# Sheet_1_2024-04-09.net
KiCad netlist of a schematic drawn in EasyEDA Pro
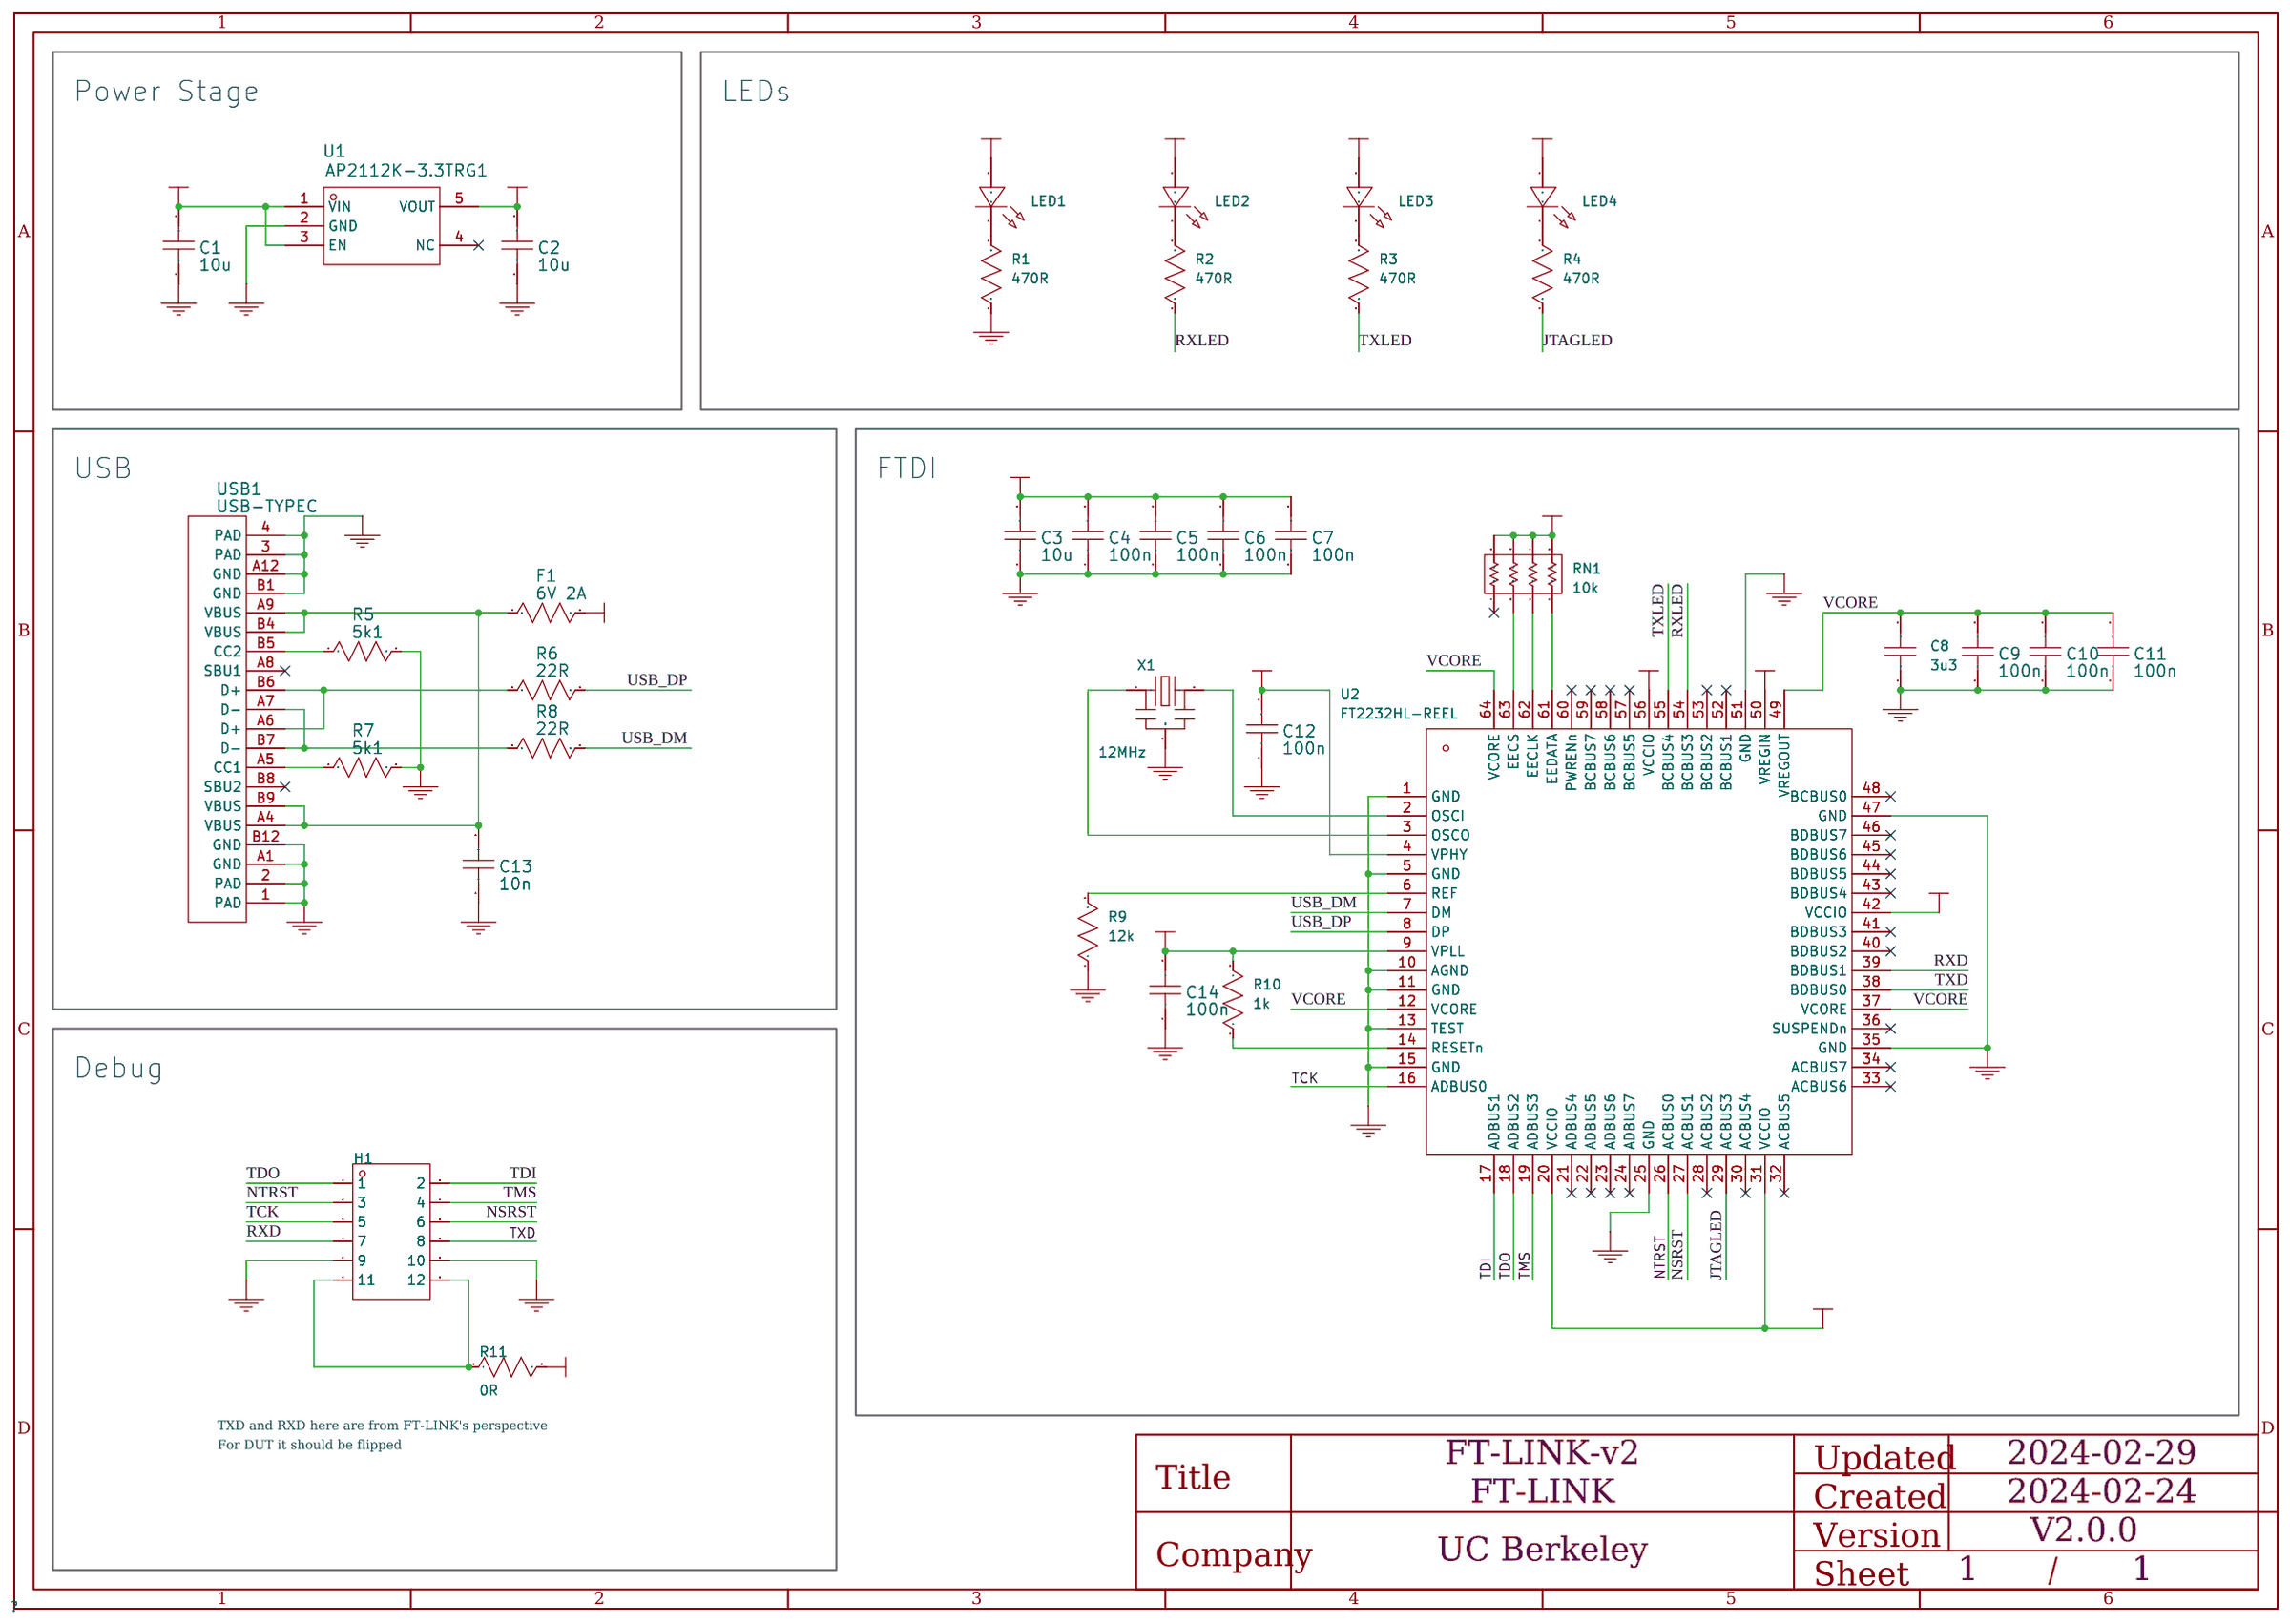
[diagram p0: schematic sheet]

(export (version "E")
  (design (tool "Eeschema 10.0.6"))
  (components
    (comp (ref "C1")
      (value "10u")
      (footprint "easyedapro:CAPA-0603")
      (fields (field (name "Manufacturer Part") "CL10A106KP8NNNC") (field (name "Manufacturer") "SAMSUNG"))
      (libsource (lib "easyedapro") (part "10u"))
    )
    (comp (ref "C2")
      (value "10u")
      (footprint "easyedapro:CAPA-0603")
      (fields (field (name "Manufacturer Part") "CL10A106KP8NNNC") (field (name "Manufacturer") "SAMSUNG"))
      (libsource (lib "easyedapro") (part "10u"))
    )
    (comp (ref "C3")
      (value "10u")
      (footprint "easyedapro:CAPA-0603")
      (fields (field (name "Manufacturer Part") "CL10A106KP8NNNC") (field (name "Manufacturer") "SAMSUNG"))
      (libsource (lib "easyedapro") (part "10u"))
    )
    (comp (ref "C4")
      (value "100n")
      (footprint "easyedapro:CAPA-0402")
      (fields (field (name "Manufacturer Part") "CL05B104KB54PNC") (field (name "Manufacturer") "SAMSUNG"))
      (libsource (lib "easyedapro") (part "100n"))
    )
    (comp (ref "C5")
      (value "100n")
      (footprint "easyedapro:CAPA-0402")
      (fields (field (name "Manufacturer Part") "CL05B104KB54PNC") (field (name "Manufacturer") "SAMSUNG"))
      (libsource (lib "easyedapro") (part "100n"))
    )
    (comp (ref "C6")
      (value "100n")
      (footprint "easyedapro:CAPA-0402")
      (fields (field (name "Manufacturer Part") "CL05B104KB54PNC") (field (name "Manufacturer") "SAMSUNG"))
      (libsource (lib "easyedapro") (part "100n"))
    )
    (comp (ref "C7")
      (value "100n")
      (footprint "easyedapro:CAPA-0402")
      (fields (field (name "Manufacturer Part") "CL05B104KB54PNC") (field (name "Manufacturer") "SAMSUNG"))
      (libsource (lib "easyedapro") (part "100n"))
    )
    (comp (ref "C8")
      (value "3u3")
      (footprint "easyedapro:CAPA-0603")
      (description "3.3uF ±10% 25V X5R")
      (fields (field (name "Manufacturer Part") "C1608X5R1E335KT000E") (field (name "Manufacturer") "TDK"))
      (libsource (lib "easyedapro") (part "CAPA-0603_3u3_25V"))
    )
    (comp (ref "C9")
      (value "100n")
      (footprint "easyedapro:CAPA-0402")
      (fields (field (name "Manufacturer Part") "CL05B104KB54PNC") (field (name "Manufacturer") "SAMSUNG"))
      (libsource (lib "easyedapro") (part "100n"))
    )
    (comp (ref "C10")
      (value "100n")
      (footprint "easyedapro:CAPA-0402")
      (fields (field (name "Manufacturer Part") "CL05B104KB54PNC") (field (name "Manufacturer") "SAMSUNG"))
      (libsource (lib "easyedapro") (part "100n"))
    )
    (comp (ref "C11")
      (value "100n")
      (footprint "easyedapro:CAPA-0402")
      (fields (field (name "Manufacturer Part") "CL05B104KB54PNC") (field (name "Manufacturer") "SAMSUNG"))
      (libsource (lib "easyedapro") (part "100n"))
    )
    (comp (ref "C12")
      (value "100n")
      (footprint "easyedapro:CAPA-0402")
      (fields (field (name "Manufacturer Part") "CL05B104KB54PNC") (field (name "Manufacturer") "SAMSUNG"))
      (libsource (lib "easyedapro") (part "100n"))
    )
    (comp (ref "C13")
      (value "10n")
      (footprint "easyedapro:CAPA-0402")
      (fields (field (name "Manufacturer Part") "CL05B103KB5NNNC") (field (name "Manufacturer") "SAMSUNG"))
      (libsource (lib "easyedapro") (part "10n"))
    )
    (comp (ref "C14")
      (value "100n")
      (footprint "easyedapro:CAPA-0402")
      (fields (field (name "Manufacturer Part") "CL05B104KB54PNC") (field (name "Manufacturer") "SAMSUNG"))
      (libsource (lib "easyedapro") (part "100n"))
    )
    (comp (ref "F1")
      (value "6V 2A")
      (footprint "easyedapro:R0805")
      (fields (field (name "Manufacturer Part") "SL0805200") (field (name "Manufacturer") "TECHFUSE"))
      (libsource (lib "easyedapro") (part "6V 2A"))
    )
    (comp (ref "H1")
      (value "~")
      (footprint "easyedapro:CONN-TH_A2541WR-2X6P")
      (fields (field (name "Manufacturer Part") "A2541WR-2x6P") (field (name "Manufacturer") "CJT 长江连接器"))
      (libsource (lib "easyedapro") (part "A2541WR-2X6P"))
    )
    (comp (ref "LED1")
      (value "~")
      (footprint "easyedapro:LED-0603")
      (description "红灯 632nm")
      (fields
        (field (name "Manufacturer Part") "19-217/R6C-AL1M2VY/3T")
        (field (name "Manufacturer") "EVERLIGHT 台湾亿光")
      )
      (libsource (lib "easyedapro") (part "LED-0603_R"))
    )
    (comp (ref "LED2")
      (value "~")
      (footprint "easyedapro:LED-0603")
      (description "白灯 高亮")
      (fields (field (name "Manufacturer Part") "LED White") (field (name "Manufacturer") "KENTO"))
      (libsource (lib "easyedapro") (part "LED-0603_W"))
    )
    (comp (ref "LED3")
      (value "~")
      (footprint "easyedapro:LED-0603")
      (description "白灯 高亮")
      (fields (field (name "Manufacturer Part") "LED White") (field (name "Manufacturer") "KENTO"))
      (libsource (lib "easyedapro") (part "LED-0603_W"))
    )
    (comp (ref "LED4")
      (value "~")
      (footprint "easyedapro:LED-0603")
      (description "蓝灯 高亮")
      (fields (field (name "Manufacturer Part") "XL-0603QBC") (field (name "Manufacturer") "KENTO"))
      (libsource (lib "easyedapro") (part "LED-0603_B"))
    )
    (comp (ref "R1")
      (value "470R")
      (footprint "easyedapro:RES-0402")
      (description "厚膜电阻 470Ω ±1% 62.5mW")
      (fields (field (name "Manufacturer Part") "0402WGF4700TCE") (field (name "Manufacturer") "UniOhm 台湾厚声"))
      (libsource (lib "easyedapro") (part "RES-0402_470R"))
    )
    (comp (ref "R2")
      (value "470R")
      (footprint "easyedapro:RES-0402")
      (description "厚膜电阻 470Ω ±1% 62.5mW")
      (fields (field (name "Manufacturer Part") "0402WGF4700TCE") (field (name "Manufacturer") "UniOhm 台湾厚声"))
      (libsource (lib "easyedapro") (part "RES-0402_470R"))
    )
    (comp (ref "R3")
      (value "470R")
      (footprint "easyedapro:RES-0402")
      (description "厚膜电阻 470Ω ±1% 62.5mW")
      (fields (field (name "Manufacturer Part") "0402WGF4700TCE") (field (name "Manufacturer") "UniOhm 台湾厚声"))
      (libsource (lib "easyedapro") (part "RES-0402_470R"))
    )
    (comp (ref "R4")
      (value "470R")
      (footprint "easyedapro:RES-0402")
      (description "厚膜电阻 470Ω ±1% 62.5mW")
      (fields (field (name "Manufacturer Part") "0402WGF4700TCE") (field (name "Manufacturer") "UniOhm 台湾厚声"))
      (libsource (lib "easyedapro") (part "RES-0402_470R"))
    )
    (comp (ref "R5")
      (value "5k1")
      (footprint "easyedapro:RES-0402")
      (fields (field (name "Manufacturer Part") "0402WGF5101TCE") (field (name "Manufacturer") "UniOhm 台湾厚声"))
      (libsource (lib "easyedapro") (part "5k1"))
    )
    (comp (ref "R6")
      (value "22R")
      (footprint "easyedapro:RES-0402")
      (fields (field (name "Manufacturer Part") "0402WGF220JTCE") (field (name "Manufacturer") "UniOhm 台湾厚声"))
      (libsource (lib "easyedapro") (part "22R"))
    )
    (comp (ref "R7")
      (value "5k1")
      (footprint "easyedapro:RES-0402")
      (fields (field (name "Manufacturer Part") "0402WGF5101TCE") (field (name "Manufacturer") "UniOhm 台湾厚声"))
      (libsource (lib "easyedapro") (part "5k1"))
    )
    (comp (ref "R8")
      (value "22R")
      (footprint "easyedapro:RES-0402")
      (fields (field (name "Manufacturer Part") "0402WGF220JTCE") (field (name "Manufacturer") "UniOhm 台湾厚声"))
      (libsource (lib "easyedapro") (part "22R"))
    )
    (comp (ref "R9")
      (value "12k")
      (footprint "easyedapro:RES-0402")
      (description "厚膜电阻 12kΩ ±1% 62.5mW")
      (fields (field (name "Manufacturer Part") "0402WGF1202TCE") (field (name "Manufacturer") "UniOhm 台湾厚声"))
      (libsource (lib "easyedapro") (part "RES-0402_12k"))
    )
    (comp (ref "R10")
      (value "1k")
      (footprint "easyedapro:RES-0402")
      (description "厚膜电阻 1kΩ ±1% 62.5mW")
      (fields (field (name "Manufacturer Part") "0402WGF1001TCE") (field (name "Manufacturer") "UniOhm 台湾厚声"))
      (libsource (lib "easyedapro") (part "RES-0402_1k"))
    )
    (comp (ref "R11")
      (value "0R")
      (footprint "easyedapro:RES-0402-TIE")
      (libsource (lib "easyedapro") (part "RES-0402_TIE"))
    )
    (comp (ref "RN1")
      (value "10k")
      (footprint "easyedapro:RES-ARRAY-SMD_0402-8P-L2.0-W1.0-BL")
      (description "10kΩ ±1% 0402x4")
      (fields (field (name "Manufacturer Part") "YC124-FR-0710KL") (field (name "Manufacturer") "YAGEO 国巨"))
      (libsource (lib "easyedapro") (part "RES-0402x4_10k"))
    )
    (comp (ref "U1")
      (value "AP2112K-3.3TRG1")
      (footprint "easyedapro:SOT-25-5_L3.0-W1.8-P0.95-LS3.0-BR")
      (fields (field (name "Manufacturer") "DIODES"))
      (libsource (lib "easyedapro") (part "AP2112K-3.3TRG1"))
    )
    (comp (ref "U2")
      (value "FT2232HL-REEL")
      (footprint "easyedapro:LQFP-64_L10.0-W10.0-P0.50-LS12.0-TL")
      (description "应用功能:USB转UART；USB转FIFO;接口协议:UART;")
      (fields (field (name "Manufacturer") "FTDI"))
      (libsource (lib "easyedapro") (part "FT2232HL"))
    )
    (comp (ref "USB1")
      (value "USB-TYPEC")
      (footprint "easyedapro:USB-C-SMD_KH-TYPE-C-16P")
      (fields
        (field (name "Manufacturer Part") "KH-TYPE-C-16P")
        (field (name "Manufacturer") "Shenzhen Kinghelm Elec")
      )
      (libsource (lib "easyedapro") (part "USB-TYPEC"))
    )
    (comp (ref "X1")
      (value "12MHz")
      (footprint "easyedapro:OSC-SMD_3P-L3.2-W1.3-P1.2-L")
      (description "频率:12MHz;内置负载电容:33pF;谐振阻抗:30Ω;")
      (fields
        (field (name "Manufacturer Part") "CSTNE12M0GH5C000R0")
        (field (name "Manufacturer") "muRata 村田")
      )
      (libsource (lib "easyedapro") (part "CSTNE12M0GH5C000R0"))
    )
  )
  (nets
    (net (code "1") (name "/JTAGLED") (class "Default")
      (node (ref "R4") (pin "1") (pinfunction "1_1") (pintype "input"))
      (node (ref "U2") (pin "29") (pinfunction "ACBUS3_29") (pintype "input"))
    )
    (net (code "2") (name "/NSRST") (class "Default")
      (node (ref "H1") (pin "6") (pinfunction "6_6") (pintype "input"))
      (node (ref "U2") (pin "27") (pinfunction "ACBUS1_27") (pintype "input"))
    )
    (net (code "3") (name "/NTRST") (class "Default")
      (node (ref "H1") (pin "3") (pinfunction "3_3") (pintype "input"))
      (node (ref "U2") (pin "26") (pinfunction "ACBUS0_26") (pintype "input"))
    )
    (net (code "4") (name "/RXD") (class "Default")
      (node (ref "H1") (pin "7") (pinfunction "7_7") (pintype "input"))
      (node (ref "U2") (pin "39") (pinfunction "BDBUS1_39") (pintype "input"))
    )
    (net (code "5") (name "/RXLED") (class "Default")
      (node (ref "R2") (pin "1") (pinfunction "1_1") (pintype "input"))
      (node (ref "U2") (pin "54") (pinfunction "BCBUS3_54") (pintype "input"))
    )
    (net (code "6") (name "/TCK") (class "Default")
      (node (ref "H1") (pin "5") (pinfunction "5_5") (pintype "input"))
      (node (ref "U2") (pin "16") (pinfunction "ADBUS0_16") (pintype "input"))
    )
    (net (code "7") (name "/TDI") (class "Default")
      (node (ref "H1") (pin "2") (pinfunction "2_2") (pintype "input"))
      (node (ref "U2") (pin "17") (pinfunction "ADBUS1_17") (pintype "input"))
    )
    (net (code "8") (name "/TDO") (class "Default")
      (node (ref "H1") (pin "1") (pinfunction "1_1") (pintype "input"))
      (node (ref "U2") (pin "18") (pinfunction "ADBUS2_18") (pintype "input"))
    )
    (net (code "9") (name "/TMS") (class "Default")
      (node (ref "H1") (pin "4") (pinfunction "4_4") (pintype "input"))
      (node (ref "U2") (pin "19") (pinfunction "ADBUS3_19") (pintype "input"))
    )
    (net (code "10") (name "/TXD") (class "Default")
      (node (ref "H1") (pin "8") (pinfunction "8_8") (pintype "input"))
      (node (ref "U2") (pin "38") (pinfunction "BDBUS0_38") (pintype "input"))
    )
    (net (code "11") (name "/TXLED") (class "Default")
      (node (ref "R3") (pin "1") (pinfunction "1_1") (pintype "input"))
      (node (ref "U2") (pin "55") (pinfunction "BCBUS4_55") (pintype "input"))
    )
    (net (code "12") (name "/USB_DM") (class "Default")
      (node (ref "R8") (pin "2") (pinfunction "2_2") (pintype "input"))
      (node (ref "U2") (pin "7") (pinfunction "DM_7") (pintype "input"))
    )
    (net (code "13") (name "/USB_DP") (class "Default")
      (node (ref "R6") (pin "2") (pinfunction "2_2") (pintype "input"))
      (node (ref "U2") (pin "8") (pinfunction "DP_8") (pintype "input"))
    )
    (net (code "14") (name "/VCORE") (class "Default")
      (node (ref "C10") (pin "2") (pinfunction "2_2") (pintype "input"))
      (node (ref "C11") (pin "2") (pinfunction "2_2") (pintype "input"))
      (node (ref "C8") (pin "1") (pinfunction "1_1") (pintype "input"))
      (node (ref "C9") (pin "2") (pinfunction "2_2") (pintype "input"))
      (node (ref "U2") (pin "12") (pinfunction "VCORE_12") (pintype "input"))
      (node (ref "U2") (pin "37") (pinfunction "VCORE_37") (pintype "input"))
      (node (ref "U2") (pin "49") (pinfunction "VREGOUT_49") (pintype "input"))
      (node (ref "U2") (pin "64") (pinfunction "VCORE_64") (pintype "input"))
    )
    (net (code "15") (name "3V3") (class "Default")
      (node (ref "C12") (pin "2") (pinfunction "2_2") (pintype "input"))
      (node (ref "C14") (pin "2") (pinfunction "2_2") (pintype "input"))
      (node (ref "C2") (pin "2") (pinfunction "2_2") (pintype "input"))
      (node (ref "C3") (pin "2") (pinfunction "2_2") (pintype "input"))
      (node (ref "C4") (pin "2") (pinfunction "2_2") (pintype "input"))
      (node (ref "C5") (pin "2") (pinfunction "2_2") (pintype "input"))
      (node (ref "C6") (pin "2") (pinfunction "2_2") (pintype "input"))
      (node (ref "C7") (pin "2") (pinfunction "2_2") (pintype "input"))
      (node (ref "LED1") (pin "2") (pinfunction "2_2") (pintype "input"))
      (node (ref "LED2") (pin "2") (pinfunction "2_2") (pintype "input"))
      (node (ref "LED3") (pin "2") (pinfunction "2_2") (pintype "input"))
      (node (ref "LED4") (pin "2") (pinfunction "2_2") (pintype "input"))
      (node (ref "R10") (pin "2") (pinfunction "2_2") (pintype "input"))
      (node (ref "R11") (pin "2") (pinfunction "2_2") (pintype "input"))
      (node (ref "RN1") (pin "5") (pinfunction "5_5") (pintype "input"))
      (node (ref "RN1") (pin "6") (pinfunction "6_6") (pintype "input"))
      (node (ref "RN1") (pin "7") (pinfunction "7_7") (pintype "input"))
      (node (ref "RN1") (pin "8") (pinfunction "8_8") (pintype "input"))
      (node (ref "U1") (pin "5") (pinfunction "VOUT_5") (pintype "input"))
      (node (ref "U2") (pin "20") (pinfunction "VCCIO_20") (pintype "input"))
      (node (ref "U2") (pin "31") (pinfunction "VCCIO_31") (pintype "input"))
      (node (ref "U2") (pin "4") (pinfunction "VPHY_4") (pintype "input"))
      (node (ref "U2") (pin "42") (pinfunction "VCCIO_42") (pintype "input"))
      (node (ref "U2") (pin "50") (pinfunction "VREGIN_50") (pintype "input"))
      (node (ref "U2") (pin "56") (pinfunction "VCCIO_56") (pintype "input"))
      (node (ref "U2") (pin "9") (pinfunction "VPLL_9") (pintype "input"))
    )
    (net (code "16") (name "5V") (class "Default")
      (node (ref "C1") (pin "2") (pinfunction "2_2") (pintype "input"))
      (node (ref "F1") (pin "2") (pinfunction "2_2") (pintype "input"))
      (node (ref "U1") (pin "1") (pinfunction "VIN_1") (pintype "input"))
      (node (ref "U1") (pin "3") (pinfunction "EN_3") (pintype "input"))
    )
    (net (code "17") (name "GND") (class "Default")
      (node (ref "C1") (pin "1") (pinfunction "1_1") (pintype "input"))
      (node (ref "C10") (pin "1") (pinfunction "1_1") (pintype "input"))
      (node (ref "C11") (pin "1") (pinfunction "1_1") (pintype "input"))
      (node (ref "C12") (pin "1") (pinfunction "1_1") (pintype "input"))
      (node (ref "C13") (pin "1") (pinfunction "1_1") (pintype "input"))
      (node (ref "C14") (pin "1") (pinfunction "1_1") (pintype "input"))
      (node (ref "C2") (pin "1") (pinfunction "1_1") (pintype "input"))
      (node (ref "C3") (pin "1") (pinfunction "1_1") (pintype "input"))
      (node (ref "C4") (pin "1") (pinfunction "1_1") (pintype "input"))
      (node (ref "C5") (pin "1") (pinfunction "1_1") (pintype "input"))
      (node (ref "C6") (pin "1") (pinfunction "1_1") (pintype "input"))
      (node (ref "C7") (pin "1") (pinfunction "1_1") (pintype "input"))
      (node (ref "C8") (pin "2") (pinfunction "2_2") (pintype "input"))
      (node (ref "C9") (pin "1") (pinfunction "1_1") (pintype "input"))
      (node (ref "H1") (pin "10") (pinfunction "10_10") (pintype "input"))
      (node (ref "H1") (pin "9") (pinfunction "9_9") (pintype "input"))
      (node (ref "R1") (pin "1") (pinfunction "1_1") (pintype "input"))
      (node (ref "R5") (pin "2") (pinfunction "2_2") (pintype "input"))
      (node (ref "R7") (pin "2") (pinfunction "2_2") (pintype "input"))
      (node (ref "R9") (pin "1") (pinfunction "1_1") (pintype "input"))
      (node (ref "U1") (pin "2") (pinfunction "GND_2") (pintype "input"))
      (node (ref "U2") (pin "1") (pinfunction "GND_1") (pintype "input"))
      (node (ref "U2") (pin "10") (pinfunction "AGND_10") (pintype "input"))
      (node (ref "U2") (pin "11") (pinfunction "GND_11") (pintype "input"))
      (node (ref "U2") (pin "13") (pinfunction "TEST_13") (pintype "input"))
      (node (ref "U2") (pin "15") (pinfunction "GND_15") (pintype "input"))
      (node (ref "U2") (pin "25") (pinfunction "GND_25") (pintype "input"))
      (node (ref "U2") (pin "35") (pinfunction "GND_35") (pintype "input"))
      (node (ref "U2") (pin "47") (pinfunction "GND_47") (pintype "input"))
      (node (ref "U2") (pin "5") (pinfunction "GND_5") (pintype "input"))
      (node (ref "U2") (pin "51") (pinfunction "GND_51") (pintype "input"))
      (node (ref "USB1") (pin "1") (pinfunction "PAD_1") (pintype "input"))
      (node (ref "USB1") (pin "2") (pinfunction "PAD_2") (pintype "input"))
      (node (ref "USB1") (pin "3") (pinfunction "PAD_3") (pintype "input"))
      (node (ref "USB1") (pin "4") (pinfunction "PAD_4") (pintype "input"))
      (node (ref "USB1") (pin "A1") (pinfunction "GND_A1") (pintype "input"))
      (node (ref "USB1") (pin "A12") (pinfunction "GND_A12") (pintype "input"))
      (node (ref "USB1") (pin "B1") (pinfunction "GND_B1") (pintype "input"))
      (node (ref "USB1") (pin "B12") (pinfunction "GND_B12") (pintype "input"))
      (node (ref "X1") (pin "2") (pinfunction "GND_2") (pintype "input"))
    )
    (net (code "18") (name "Net-(C13-Pad2)") (class "Default")
      (node (ref "C13") (pin "2") (pinfunction "2_2") (pintype "input"))
      (node (ref "F1") (pin "1") (pinfunction "1_1") (pintype "input"))
      (node (ref "USB1") (pin "A4") (pinfunction "VBUS_A4") (pintype "input"))
      (node (ref "USB1") (pin "A9") (pinfunction "VBUS_A9") (pintype "input"))
      (node (ref "USB1") (pin "B4") (pinfunction "VBUS_B4") (pintype "input"))
      (node (ref "USB1") (pin "B9") (pinfunction "VBUS_B9") (pintype "input"))
    )
    (net (code "19") (name "Net-(H1-Pad11)") (class "Default")
      (node (ref "H1") (pin "11") (pinfunction "11_11") (pintype "input"))
      (node (ref "H1") (pin "12") (pinfunction "12_12") (pintype "input"))
      (node (ref "R11") (pin "1") (pinfunction "1_1") (pintype "input"))
    )
    (net (code "20") (name "Net-(LED1-Pad1)") (class "Default")
      (node (ref "LED1") (pin "1") (pinfunction "1_1") (pintype "input"))
      (node (ref "R1") (pin "2") (pinfunction "2_2") (pintype "input"))
    )
    (net (code "21") (name "Net-(LED2-Pad1)") (class "Default")
      (node (ref "LED2") (pin "1") (pinfunction "1_1") (pintype "input"))
      (node (ref "R2") (pin "2") (pinfunction "2_2") (pintype "input"))
    )
    (net (code "22") (name "Net-(LED3-Pad1)") (class "Default")
      (node (ref "LED3") (pin "1") (pinfunction "1_1") (pintype "input"))
      (node (ref "R3") (pin "2") (pinfunction "2_2") (pintype "input"))
    )
    (net (code "23") (name "Net-(LED4-Pad1)") (class "Default")
      (node (ref "LED4") (pin "1") (pinfunction "1_1") (pintype "input"))
      (node (ref "R4") (pin "2") (pinfunction "2_2") (pintype "input"))
    )
    (net (code "24") (name "Net-(R6-Pad1)") (class "Default")
      (node (ref "R6") (pin "1") (pinfunction "1_1") (pintype "input"))
      (node (ref "USB1") (pin "A6") (pinfunction "D+_A6") (pintype "input"))
      (node (ref "USB1") (pin "B6") (pinfunction "D+_B6") (pintype "input"))
    )
    (net (code "25") (name "Net-(R8-Pad1)") (class "Default")
      (node (ref "R8") (pin "1") (pinfunction "1_1") (pintype "input"))
      (node (ref "USB1") (pin "A7") (pinfunction "D-_A7") (pintype "input"))
      (node (ref "USB1") (pin "B7") (pinfunction "D-_B7") (pintype "input"))
    )
    (net (code "26") (name "Net-(U2-EECLK)") (class "Default")
      (node (ref "RN1") (pin "2") (pinfunction "2_2") (pintype "input"))
      (node (ref "U2") (pin "62") (pinfunction "EECLK_62") (pintype "input"))
    )
    (net (code "27") (name "Net-(U2-EECS)") (class "Default")
      (node (ref "RN1") (pin "3") (pinfunction "3_3") (pintype "input"))
      (node (ref "U2") (pin "63") (pinfunction "EECS_63") (pintype "input"))
    )
    (net (code "28") (name "Net-(U2-EEDATA)") (class "Default")
      (node (ref "RN1") (pin "1") (pinfunction "1_1") (pintype "input"))
      (node (ref "U2") (pin "61") (pinfunction "EEDATA_61") (pintype "input"))
    )
    (net (code "29") (name "Net-(U2-OSCI)") (class "Default")
      (node (ref "U2") (pin "2") (pinfunction "OSCI_2") (pintype "input"))
      (node (ref "X1") (pin "3") (pinfunction "OUT_3") (pintype "input"))
    )
    (net (code "30") (name "Net-(U2-OSCO)") (class "Default")
      (node (ref "U2") (pin "3") (pinfunction "OSCO_3") (pintype "input"))
      (node (ref "X1") (pin "1") (pinfunction "IN_1") (pintype "input"))
    )
    (net (code "31") (name "Net-(U2-REF)") (class "Default")
      (node (ref "R9") (pin "2") (pinfunction "2_2") (pintype "input"))
      (node (ref "U2") (pin "6") (pinfunction "REF_6") (pintype "input"))
    )
    (net (code "32") (name "Net-(U2-RESETn)") (class "Default")
      (node (ref "R10") (pin "1") (pinfunction "1_1") (pintype "input"))
      (node (ref "U2") (pin "14") (pinfunction "RESETn_14") (pintype "input"))
    )
    (net (code "33") (name "Net-(USB1-CC1)") (class "Default")
      (node (ref "R7") (pin "1") (pinfunction "1_1") (pintype "input"))
      (node (ref "USB1") (pin "A5") (pinfunction "CC1_A5") (pintype "input"))
    )
    (net (code "34") (name "Net-(USB1-CC2)") (class "Default")
      (node (ref "R5") (pin "1") (pinfunction "1_1") (pintype "input"))
      (node (ref "USB1") (pin "B5") (pinfunction "CC2_B5") (pintype "input"))
    )
    (net (code "35") (name "unconnected-(RN1-Pad4)") (class "Default")
      (node (ref "RN1") (pin "4") (pinfunction "4_4") (pintype "input+no_connect"))
    )
    (net (code "36") (name "unconnected-(U1-NC-Pad4)") (class "Default")
      (node (ref "U1") (pin "4") (pinfunction "NC_4") (pintype "input+no_connect"))
    )
    (net (code "37") (name "unconnected-(U2-ACBUS2-Pad28)") (class "Default")
      (node (ref "U2") (pin "28") (pinfunction "ACBUS2_28") (pintype "input+no_connect"))
    )
    (net (code "38") (name "unconnected-(U2-ACBUS4-Pad30)") (class "Default")
      (node (ref "U2") (pin "30") (pinfunction "ACBUS4_30") (pintype "input+no_connect"))
    )
    (net (code "39") (name "unconnected-(U2-ACBUS5-Pad32)") (class "Default")
      (node (ref "U2") (pin "32") (pinfunction "ACBUS5_32") (pintype "input+no_connect"))
    )
    (net (code "40") (name "unconnected-(U2-ACBUS6-Pad33)") (class "Default")
      (node (ref "U2") (pin "33") (pinfunction "ACBUS6_33") (pintype "input+no_connect"))
    )
    (net (code "41") (name "unconnected-(U2-ACBUS7-Pad34)") (class "Default")
      (node (ref "U2") (pin "34") (pinfunction "ACBUS7_34") (pintype "input+no_connect"))
    )
    (net (code "42") (name "unconnected-(U2-ADBUS4-Pad21)") (class "Default")
      (node (ref "U2") (pin "21") (pinfunction "ADBUS4_21") (pintype "input+no_connect"))
    )
    (net (code "43") (name "unconnected-(U2-ADBUS5-Pad22)") (class "Default")
      (node (ref "U2") (pin "22") (pinfunction "ADBUS5_22") (pintype "input+no_connect"))
    )
    (net (code "44") (name "unconnected-(U2-ADBUS6-Pad23)") (class "Default")
      (node (ref "U2") (pin "23") (pinfunction "ADBUS6_23") (pintype "input+no_connect"))
    )
    (net (code "45") (name "unconnected-(U2-ADBUS7-Pad24)") (class "Default")
      (node (ref "U2") (pin "24") (pinfunction "ADBUS7_24") (pintype "input+no_connect"))
    )
    (net (code "46") (name "unconnected-(U2-BCBUS0-Pad48)") (class "Default")
      (node (ref "U2") (pin "48") (pinfunction "BCBUS0_48") (pintype "input+no_connect"))
    )
    (net (code "47") (name "unconnected-(U2-BCBUS1-Pad52)") (class "Default")
      (node (ref "U2") (pin "52") (pinfunction "BCBUS1_52") (pintype "input+no_connect"))
    )
    (net (code "48") (name "unconnected-(U2-BCBUS2-Pad53)") (class "Default")
      (node (ref "U2") (pin "53") (pinfunction "BCBUS2_53") (pintype "input+no_connect"))
    )
    (net (code "49") (name "unconnected-(U2-BCBUS5-Pad57)") (class "Default")
      (node (ref "U2") (pin "57") (pinfunction "BCBUS5_57") (pintype "input+no_connect"))
    )
    (net (code "50") (name "unconnected-(U2-BCBUS6-Pad58)") (class "Default")
      (node (ref "U2") (pin "58") (pinfunction "BCBUS6_58") (pintype "input+no_connect"))
    )
    (net (code "51") (name "unconnected-(U2-BCBUS7-Pad59)") (class "Default")
      (node (ref "U2") (pin "59") (pinfunction "BCBUS7_59") (pintype "input+no_connect"))
    )
    (net (code "52") (name "unconnected-(U2-BDBUS2-Pad40)") (class "Default")
      (node (ref "U2") (pin "40") (pinfunction "BDBUS2_40") (pintype "input+no_connect"))
    )
    (net (code "53") (name "unconnected-(U2-BDBUS3-Pad41)") (class "Default")
      (node (ref "U2") (pin "41") (pinfunction "BDBUS3_41") (pintype "input+no_connect"))
    )
    (net (code "54") (name "unconnected-(U2-BDBUS4-Pad43)") (class "Default")
      (node (ref "U2") (pin "43") (pinfunction "BDBUS4_43") (pintype "input+no_connect"))
    )
    (net (code "55") (name "unconnected-(U2-BDBUS5-Pad44)") (class "Default")
      (node (ref "U2") (pin "44") (pinfunction "BDBUS5_44") (pintype "input+no_connect"))
    )
    (net (code "56") (name "unconnected-(U2-BDBUS6-Pad45)") (class "Default")
      (node (ref "U2") (pin "45") (pinfunction "BDBUS6_45") (pintype "input+no_connect"))
    )
    (net (code "57") (name "unconnected-(U2-BDBUS7-Pad46)") (class "Default")
      (node (ref "U2") (pin "46") (pinfunction "BDBUS7_46") (pintype "input+no_connect"))
    )
    (net (code "58") (name "unconnected-(U2-PWRENn-Pad60)") (class "Default")
      (node (ref "U2") (pin "60") (pinfunction "PWRENn_60") (pintype "input+no_connect"))
    )
    (net (code "59") (name "unconnected-(U2-SUSPENDn-Pad36)") (class "Default")
      (node (ref "U2") (pin "36") (pinfunction "SUSPENDn_36") (pintype "input+no_connect"))
    )
    (net (code "60") (name "unconnected-(USB1-SBU1-PadA8)") (class "Default")
      (node (ref "USB1") (pin "A8") (pinfunction "SBU1_A8") (pintype "input+no_connect"))
    )
    (net (code "61") (name "unconnected-(USB1-SBU2-PadB8)") (class "Default")
      (node (ref "USB1") (pin "B8") (pinfunction "SBU2_B8") (pintype "input+no_connect"))
    )
  )
)
